# efr32_radio_interface.net
KiCad netlist of a schematic drawn in Altium Designer
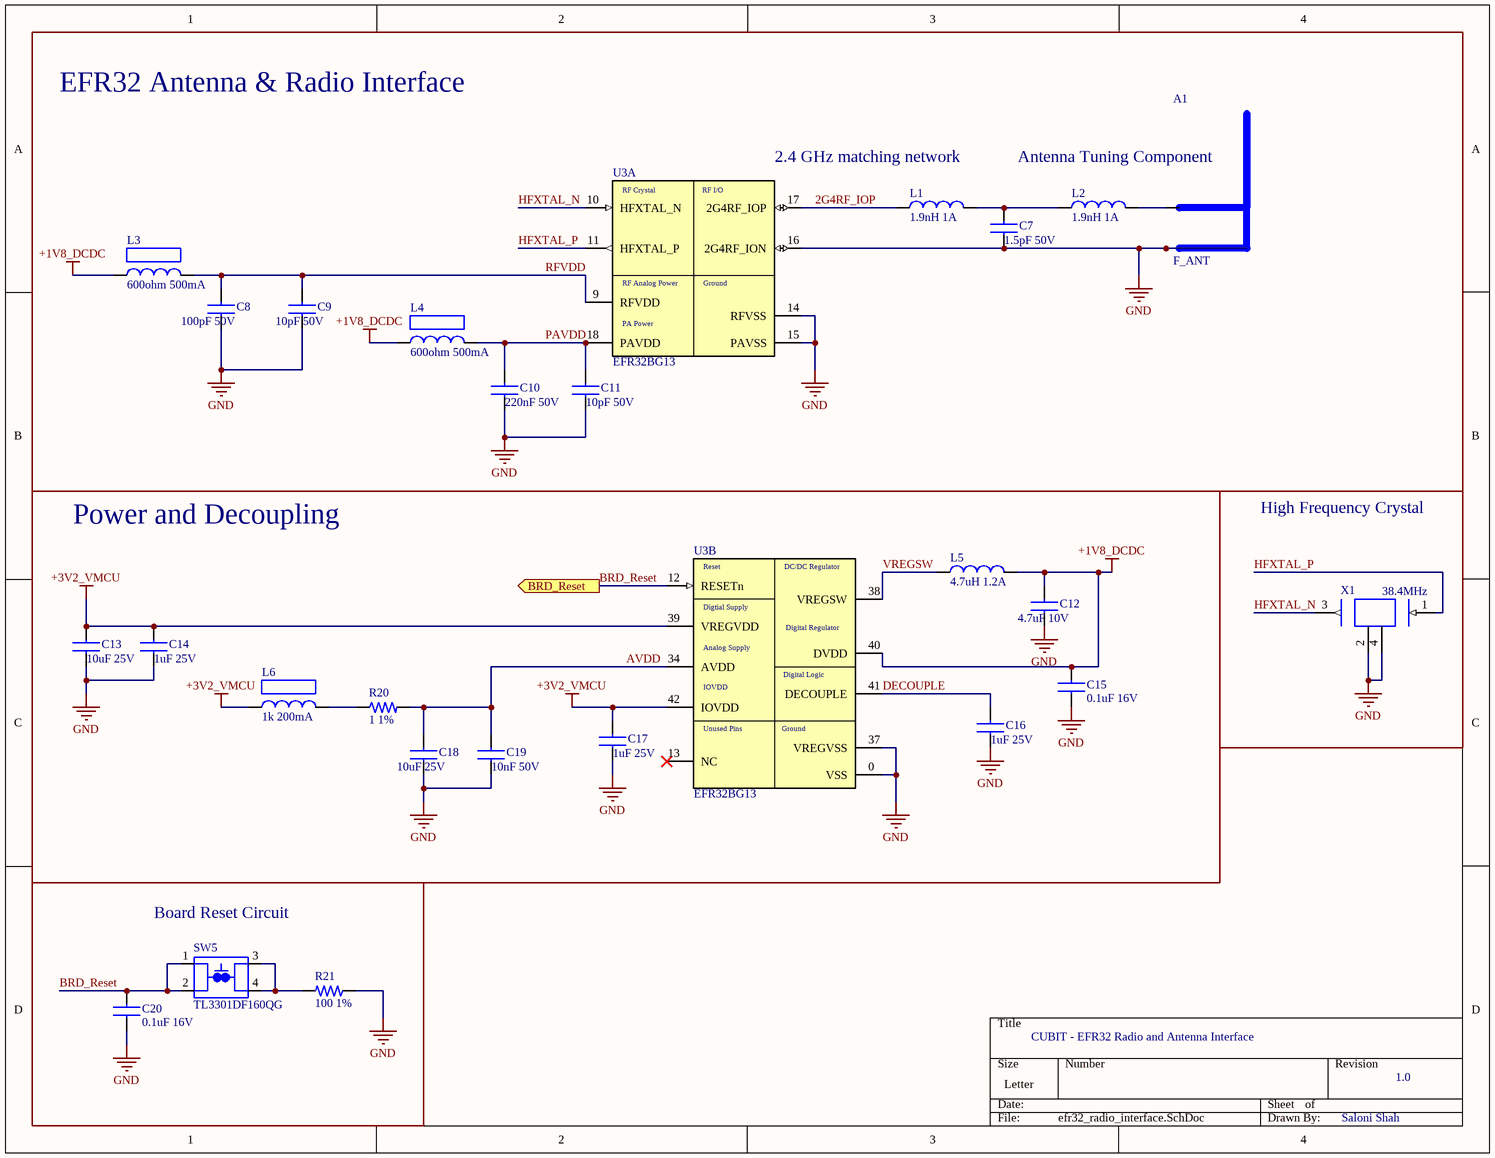
[diagram p0: efr32_radio_interface.SchDoc]

(export (version "E")
  (design (tool "Eeschema 10.0.6"))
  (components
    (comp (ref "A1")
      (value "F_ANT")
      (footprint "F_ANTENNA_FOOTPRINT")
      (libsource (lib "LPEDT_proj_lib") (part "F_ANT"))
    )
    (comp (ref "C7")
      (value "1.5pF 50V")
      (footprint "CAP_0402_1mm")
      (description "Cap Ceramic 1.5pF 50V C0G 5% Pad SMD 0402 125C Automotive T/R")
      (fields
        (field (name "MANUFACTURER") "Murata")
        (field (name "MANUFACTURER PART NUMBER") "GCM1555C1H1R5JA16D")
      )
      (libsource (lib "LPEDT_proj_lib") (part "GCM1555C1H1R5JA16D"))
    )
    (comp (ref "C8")
      (value "100pF 50V")
      (footprint "LPEDT_proj_lib:CAP_0805_02X125")
      (description "Cap 0.1nF ±10% 50V X7R 0805")
      (fields
        (field (name "MANUFACTURER") "Yageo")
        (field (name "MANUFACTURER PART NUMBER") "CC0805KRX7R9BB101")
      )
      (libsource (lib "LPEDT_proj_lib") (part "CC0805KRX7R9BB101"))
    )
    (comp (ref "C9")
      (value "10pF 50V")
      (footprint "LPEDT_proj_lib:CAP_0805_02X125")
      (description "Cap Ceramic 10pF 50V X7R 10% SMD 0805 125°C Paper T/R")
      (fields
        (field (name "MANUFACTURER") "KEMET")
        (field (name "MANUFACTURER PART NUMBER") "C0805C100K5RACTU")
      )
      (libsource (lib "LPEDT_proj_lib") (part "C0805C100K5RACTU"))
    )
    (comp (ref "C10")
      (value "220nF 50V")
      (footprint "LPEDT_proj_lib:CAP_0805_02X125")
      (description "Cap 220nF ±10% 50V X7R 0805")
      (fields
        (field (name "MANUFACTURER") "Yageo")
        (field (name "MANUFACTURER PART NUMBER") "CC0805KKX7R9BB224")
      )
      (libsource (lib "LPEDT_proj_lib") (part "CC0805KKX7R9BB224"))
    )
    (comp (ref "C11")
      (value "10pF 50V")
      (footprint "LPEDT_proj_lib:CAP_0805_02X125")
      (description "Cap Ceramic 10pF 50V X7R 10% SMD 0805 125°C Paper T/R")
      (fields
        (field (name "MANUFACTURER") "KEMET")
        (field (name "MANUFACTURER PART NUMBER") "C0805C100K5RACTU")
      )
      (libsource (lib "LPEDT_proj_lib") (part "C0805C100K5RACTU"))
    )
    (comp (ref "C12")
      (value "4.7uF 10V")
      (footprint "LPEDT_proj_lib:CAP_0603_1MM")
      (description "Cap CL10 Series 4.7 uF 10 V ±10 % Tolerance X5R SMT Multilayer Ceramic Capacitor")
      (fields
        (field (name "MANUFACTURER") "Samsung")
        (field (name "MANUFACTURER PART NUMBER") "CL10A475KP8NNNC")
      )
      (libsource (lib "LPEDT_proj_lib") (part "CL10A475KP8NNNC"))
    )
    (comp (ref "C13")
      (value "10uF 25V")
      (footprint "LPEDT_proj_lib:CAP_0805_02X125")
      (description "Cap 0805 25 V 10 uF ±20% Tolerance X5R Monolithic Ceramic Chip Capacitor")
      (fields
        (field (name "MANUFACTURER") "Murata")
        (field (name "MANUFACTURER PART NUMBER") "GRM21BR61E106KA73K")
      )
      (libsource (lib "LPEDT_proj_lib") (part "GRM21BR61E106KA73K"))
    )
    (comp (ref "C14")
      (value "1uF 25V")
      (footprint "LPEDT_proj_lib:CAP_0805_02X125")
      (description "Cap 1 µF ±10% 25V Ceramic Capacitor X5R 0805 (2012 Metric)")
      (fields
        (field (name "MANUFACTURER") "Murata")
        (field (name "MANUFACTURER PART NUMBER") "GRM216R61E105KA12D")
      )
      (libsource (lib "LPEDT_proj_lib") (part "GRM216R61E105KA12D"))
    )
    (comp (ref "C15")
      (value "0.1uF 16V")
      (footprint "LPEDT_proj_lib:CAP_0603_1MM")
      (description "Cap Ceramic 0.1uF 16V X7R 10% SMD 0805 125°C Paper T/R")
      (fields
        (field (name "MANUFACTURER") "KEMET")
        (field (name "MANUFACTURER PART NUMBER") "C0805C104K4RACAUTO")
      )
      (libsource (lib "LPEDT_proj_lib") (part "C0805C104K4RACAUTO"))
    )
    (comp (ref "C16")
      (value "1uF 25V")
      (footprint "LPEDT_proj_lib:CAP_0805_02X125")
      (description "Cap 1 µF ±10% 25V Ceramic Capacitor X5R 0805 (2012 Metric)")
      (fields
        (field (name "MANUFACTURER") "Murata")
        (field (name "MANUFACTURER PART NUMBER") "GRM216R61E105KA12D")
      )
      (libsource (lib "LPEDT_proj_lib") (part "GRM216R61E105KA12D"))
    )
    (comp (ref "C17")
      (value "1uF 25V")
      (footprint "LPEDT_proj_lib:CAP_0805_02X125")
      (description "Cap 1 µF ±10% 25V Ceramic Capacitor X5R 0805 (2012 Metric)")
      (fields
        (field (name "MANUFACTURER") "Murata")
        (field (name "MANUFACTURER PART NUMBER") "GRM216R61E105KA12D")
      )
      (libsource (lib "LPEDT_proj_lib") (part "GRM216R61E105KA12D"))
    )
    (comp (ref "C18")
      (value "10uF 25V")
      (footprint "LPEDT_proj_lib:CAP_0805_02X125")
      (description "Cap 0805 25 V 10 uF ±20% Tolerance X5R Monolithic Ceramic Chip Capacitor")
      (fields
        (field (name "MANUFACTURER") "Murata")
        (field (name "MANUFACTURER PART NUMBER") "GRM21BR61E106KA73K")
      )
      (libsource (lib "LPEDT_proj_lib") (part "GRM21BR61E106KA73K"))
    )
    (comp (ref "C19")
      (value "10nF 50V")
      (footprint "LPEDT_proj_lib:CAP_0805_02X125")
      (description "Cap 10nF ±10% 50V X7R 0805")
      (fields
        (field (name "MANUFACTURER") "Samsung")
        (field (name "MANUFACTURER PART NUMBER") "CL21B103KBCNNNC")
      )
      (libsource (lib "LPEDT_proj_lib") (part "CL21B103KBCNNNC"))
    )
    (comp (ref "C20")
      (value "0.1uF 16V")
      (footprint "LPEDT_proj_lib:CAP_0603_1MM")
      (description "Cap Ceramic 0.1uF 16V X7R 10% SMD 0805 125°C Paper T/R")
      (fields
        (field (name "MANUFACTURER") "KEMET")
        (field (name "MANUFACTURER PART NUMBER") "C0805C104K4RACAUTO")
      )
      (libsource (lib "LPEDT_proj_lib") (part "C0805C104K4RACAUTO"))
    )
    (comp (ref "L1")
      (value "1.9nH 1A")
      (footprint "CAP_0402_1mm")
      (description "Inductor Chip 1.9nH 0.3nH Tolerance 2-Pin 0402 Paper T/R")
      (fields
        (field (name "MANUFACTURER") "Murata")
        (field (name "MANUFACTURER PART NUMBER") "LQG15WZ1N9S02D")
      )
      (libsource (lib "LPEDT_proj_lib") (part "LQG15WZ1N9S02D"))
    )
    (comp (ref "L2")
      (value "1.9nH 1A")
      (footprint "CAP_0402_1mm")
      (description "Inductor Chip 1.9nH 0.3nH Tolerance 2-Pin 0402 Paper T/R")
      (fields
        (field (name "MANUFACTURER") "Murata")
        (field (name "MANUFACTURER PART NUMBER") "LQG15WZ1N9S02D")
      )
      (libsource (lib "LPEDT_proj_lib") (part "LQG15WZ1N9S02D"))
    )
    (comp (ref "L3")
      (value "600ohm 500mA")
      (footprint "IND_FERRITE_0603_1.6x0.4")
      (description "Ferrite Beads 0603 600Ω ±25% DCR=0.38Ω 500mA")
      (fields
        (field (name "MANUFACTURER") "Murata")
        (field (name "MANUFACTURER PART NUMBER") "BLM18AG601SN1D")
      )
      (libsource (lib "LPEDT_proj_lib") (part "BLM18AG601SN1D"))
    )
    (comp (ref "L4")
      (value "600ohm 500mA")
      (footprint "IND_FERRITE_0603_1.6x0.4")
      (description "Ferrite Beads 0603 600Ω ±25% DCR=0.38Ω 500mA")
      (fields
        (field (name "MANUFACTURER") "Murata")
        (field (name "MANUFACTURER PART NUMBER") "BLM18AG601SN1D")
      )
      (libsource (lib "LPEDT_proj_lib") (part "BLM18AG601SN1D"))
    )
    (comp (ref "L5")
      (value "4.7uH 1.2A")
      (footprint "2_IND_32X25")
      (description "Inductor FIXED IND 4.7UH 1.2A 186 MOHM")
      (fields
        (field (name "MANUFACTURER") "Murata")
        (field (name "MANUFACTURER PART NUMBER") "LQH32PH4R7NNCL")
      )
      (libsource (lib "LPEDT_proj_lib") (part "LQH32PH4R7NNCL"))
    )
    (comp (ref "L6")
      (value "1k 200mA")
      (footprint "LPEDT_proj_lib:CAP_0603_1MM")
      (description "Ferrite Beads WE-CBF 0603 SMD Bead 100MHz 1000Ohm 200mA")
      (fields
        (field (name "MANUFACTURER") "Wurth Electronics")
        (field (name "MANUFACTURER PART NUMBER") "74279266")
      )
      (libsource (lib "LPEDT_proj_lib") (part "74279266"))
    )
    (comp (ref "R20")
      (value "1 1%")
      (footprint "LPEDT_proj_lib:CAP_0603_1MM")
      (description "Res 1 Ohm 1% 1/10W ±200ppm/°C Molded SMD SMD Paper T/R")
      (fields
        (field (name "MANUFACTURER") "Yageo")
        (field (name "MANUFACTURER PART NUMBER") "RC0603FR-101RL")
      )
      (libsource (lib "LPEDT_proj_lib") (part "RC0603FR-101RL"))
    )
    (comp (ref "R21")
      (value "100 1%")
      (footprint "2_Chip_0603_RMCF")
      (description "Res 100 Ohm 1% 1/10W ±100ppm/°C Molded SMD SMD Paper T/R")
      (fields
        (field (name "MANUFACTURER") "Stackpole Electronics")
        (field (name "MANUFACTURER PART NUMBER") "RMCF0603FT100R")
      )
      (libsource (lib "LPEDT_proj_lib") (part "RMCF0603FT100R"))
    )
    (comp (ref "SW5")
      (value "TL3301DF160QG")
      (footprint "SW_TL3301DF160QG")
      (description "Tactile Switch SPST-NO Top Actuated Surface Mount")
      (fields (field (name "MF") "E-Switch"))
      (libsource (lib "LPEDT_proj_lib") (part "TL3301DF160QG"))
    )
    (comp (ref "U3")
      (value "EFR32BG13")
      (footprint "48-QFN_7x7")
      (description "Blue Gecko QFN48 2.4 G 19 dB BLE/Proprietary 512 kB 64 kB(RAM) 31GPIO")
      (fields
        (field (name "MANUFACTURER") "Silicon Labs")
        (field (name "MANUFACTURER PART NUMBER") "EFR32BG13P732F512GM48-D")
      )
      (libsource (lib "LPEDT_proj_lib") (part "EFR32BG13P732F512GM48-D"))
    )
    (comp (ref "X1")
      (value "38.4MHz")
      (footprint "OSC_38.4MHz")
      (description "Crystal 38.4000MHZ 10PF SMD")
      (fields
        (field (name "MANUFACTURER") "Raltron Electronics")
        (field (name "MANUFACTURER PART NUMBER") "RH100-38.400-10-F-1010-TR")
      )
      (libsource (lib "LPEDT_proj_lib") (part "RH100-38.400-10-F-1010-TR"))
    )
  )
  (nets
    (net (code "1") (name "+1V8_DCDC") (class "Default")
      (node (ref "C12") (pin "1") (pinfunction "1_1") (pintype "passive"))
      (node (ref "C15") (pin "1") (pinfunction "1_1") (pintype "passive"))
      (node (ref "L3") (pin "1") (pinfunction "1_1") (pintype "passive"))
      (node (ref "L4") (pin "1") (pinfunction "1_1") (pintype "passive"))
      (node (ref "L5") (pin "2") (pinfunction "2_2") (pintype "passive"))
      (node (ref "U3") (pin "40") (pinfunction "DVDD_40") (pintype "power_in"))
    )
    (net (code "2") (name "+3V2_VMCU") (class "Default")
      (node (ref "C13") (pin "1") (pinfunction "1_1") (pintype "passive"))
      (node (ref "C14") (pin "1") (pinfunction "1_1") (pintype "passive"))
      (node (ref "C17") (pin "1") (pinfunction "1_1") (pintype "passive"))
      (node (ref "L6") (pin "1") (pinfunction "1_1") (pintype "passive"))
      (node (ref "U3") (pin "39") (pinfunction "VREGVDD_39") (pintype "power_in"))
      (node (ref "U3") (pin "42") (pinfunction "IOVDD_42") (pintype "power_in"))
    )
    (net (code "3") (name "/2G4RF_IOP") (class "Default")
      (node (ref "L1") (pin "1") (pinfunction "1_1") (pintype "passive"))
      (node (ref "U3") (pin "17") (pinfunction "2G4RF_IOP_17") (pintype "bidirectional"))
    )
    (net (code "4") (name "/AVDD") (class "Default")
      (node (ref "C18") (pin "1") (pinfunction "1_1") (pintype "passive"))
      (node (ref "C19") (pin "1") (pinfunction "1_1") (pintype "passive"))
      (node (ref "R20") (pin "2") (pinfunction "2_2") (pintype "passive"))
      (node (ref "U3") (pin "34") (pinfunction "AVDD_34") (pintype "power_in"))
    )
    (net (code "5") (name "/BRD_Reset") (class "Default")
      (node (ref "C20") (pin "1") (pinfunction "1_1") (pintype "passive"))
      (node (ref "SW5") (pin "1") (pinfunction "1_1") (pintype "passive"))
      (node (ref "SW5") (pin "2") (pinfunction "2_2") (pintype "passive"))
      (node (ref "U3") (pin "12") (pinfunction "RESETn_12") (pintype "input"))
    )
    (net (code "6") (name "/DECOUPLE") (class "Default")
      (node (ref "C16") (pin "1") (pinfunction "1_1") (pintype "passive"))
      (node (ref "U3") (pin "41") (pinfunction "DECOUPLE_41") (pintype "power_in"))
    )
    (net (code "7") (name "/HFXTAL_N") (class "Default")
      (node (ref "U3") (pin "10") (pinfunction "HFXTAL_N_10") (pintype "input"))
      (node (ref "X1") (pin "3") (pintype "output"))
    )
    (net (code "8") (name "/HFXTAL_P") (class "Default")
      (node (ref "U3") (pin "11") (pinfunction "HFXTAL_P_11") (pintype "output"))
      (node (ref "X1") (pin "1") (pintype "input"))
    )
    (net (code "9") (name "/PAVDD") (class "Default")
      (node (ref "C10") (pin "1") (pinfunction "1_1") (pintype "passive"))
      (node (ref "C11") (pin "1") (pinfunction "1_1") (pintype "passive"))
      (node (ref "L4") (pin "2") (pinfunction "2_2") (pintype "passive"))
      (node (ref "U3") (pin "18") (pinfunction "PAVDD_18") (pintype "power_in"))
    )
    (net (code "10") (name "/RFVDD") (class "Default")
      (node (ref "C8") (pin "1") (pinfunction "1_1") (pintype "passive"))
      (node (ref "C9") (pin "1") (pinfunction "1_1") (pintype "passive"))
      (node (ref "L3") (pin "2") (pinfunction "2_2") (pintype "passive"))
      (node (ref "U3") (pin "9") (pinfunction "RFVDD_9") (pintype "power_in"))
    )
    (net (code "11") (name "/VREGSW") (class "Default")
      (node (ref "L5") (pin "1") (pinfunction "1_1") (pintype "passive"))
      (node (ref "U3") (pin "38") (pinfunction "VREGSW_38") (pintype "power_in"))
    )
    (net (code "12") (name "GND") (class "Default")
      (node (ref "A1") (pin "GND") (pinfunction "GND_GND") (pintype "passive"))
      (node (ref "C10") (pin "2") (pinfunction "2_2") (pintype "passive"))
      (node (ref "C11") (pin "2") (pinfunction "2_2") (pintype "passive"))
      (node (ref "C12") (pin "2") (pinfunction "2_2") (pintype "passive"))
      (node (ref "C13") (pin "2") (pinfunction "2_2") (pintype "passive"))
      (node (ref "C14") (pin "2") (pinfunction "2_2") (pintype "passive"))
      (node (ref "C15") (pin "2") (pinfunction "2_2") (pintype "passive"))
      (node (ref "C16") (pin "2") (pinfunction "2_2") (pintype "passive"))
      (node (ref "C17") (pin "2") (pinfunction "2_2") (pintype "passive"))
      (node (ref "C18") (pin "2") (pinfunction "2_2") (pintype "passive"))
      (node (ref "C19") (pin "2") (pinfunction "2_2") (pintype "passive"))
      (node (ref "C20") (pin "2") (pinfunction "2_2") (pintype "passive"))
      (node (ref "C7") (pin "2") (pinfunction "2_2") (pintype "passive"))
      (node (ref "C8") (pin "2") (pinfunction "2_2") (pintype "passive"))
      (node (ref "C9") (pin "2") (pinfunction "2_2") (pintype "passive"))
      (node (ref "R21") (pin "1") (pinfunction "1_1") (pintype "passive"))
      (node (ref "U3") (pin "0") (pinfunction "VSS_0") (pintype "power_in"))
      (node (ref "U3") (pin "14") (pinfunction "RFVSS_14") (pintype "power_in"))
      (node (ref "U3") (pin "15") (pinfunction "PAVSS_15") (pintype "power_in"))
      (node (ref "U3") (pin "16") (pinfunction "2G4RF_ION_16") (pintype "bidirectional"))
      (node (ref "U3") (pin "37") (pinfunction "VREGVSS_37") (pintype "power_in"))
      (node (ref "X1") (pin "2") (pintype "power_in"))
      (node (ref "X1") (pin "4") (pintype "power_in"))
    )
    (net (code "13") (name "Net-(A1-PadFEED)") (class "Default")
      (node (ref "A1") (pin "FEED") (pinfunction "FEED_FEED") (pintype "passive"))
      (node (ref "L2") (pin "2") (pinfunction "2_2") (pintype "passive"))
    )
    (net (code "14") (name "Net-(C7-Pad1)") (class "Default")
      (node (ref "C7") (pin "1") (pinfunction "1_1") (pintype "passive"))
      (node (ref "L1") (pin "2") (pinfunction "2_2") (pintype "passive"))
      (node (ref "L2") (pin "1") (pinfunction "1_1") (pintype "passive"))
    )
    (net (code "15") (name "Net-(L6-Pad2)") (class "Default")
      (node (ref "L6") (pin "2") (pinfunction "2_2") (pintype "passive"))
      (node (ref "R20") (pin "1") (pinfunction "1_1") (pintype "passive"))
    )
    (net (code "16") (name "Net-(R21-Pad2)") (class "Default")
      (node (ref "R21") (pin "2") (pinfunction "2_2") (pintype "passive"))
      (node (ref "SW5") (pin "3") (pinfunction "3_3") (pintype "passive"))
      (node (ref "SW5") (pin "4") (pinfunction "4_4") (pintype "passive"))
    )
    (net (code "17") (name "unconnected-(U3B-NC-Pad13)") (class "Default")
      (node (ref "U3") (pin "13") (pinfunction "NC_13") (pintype "passive+no_connect"))
    )
  )
)
